# thermometer_temp_sense.net
KiCad netlist of a schematic drawn in EAGLE
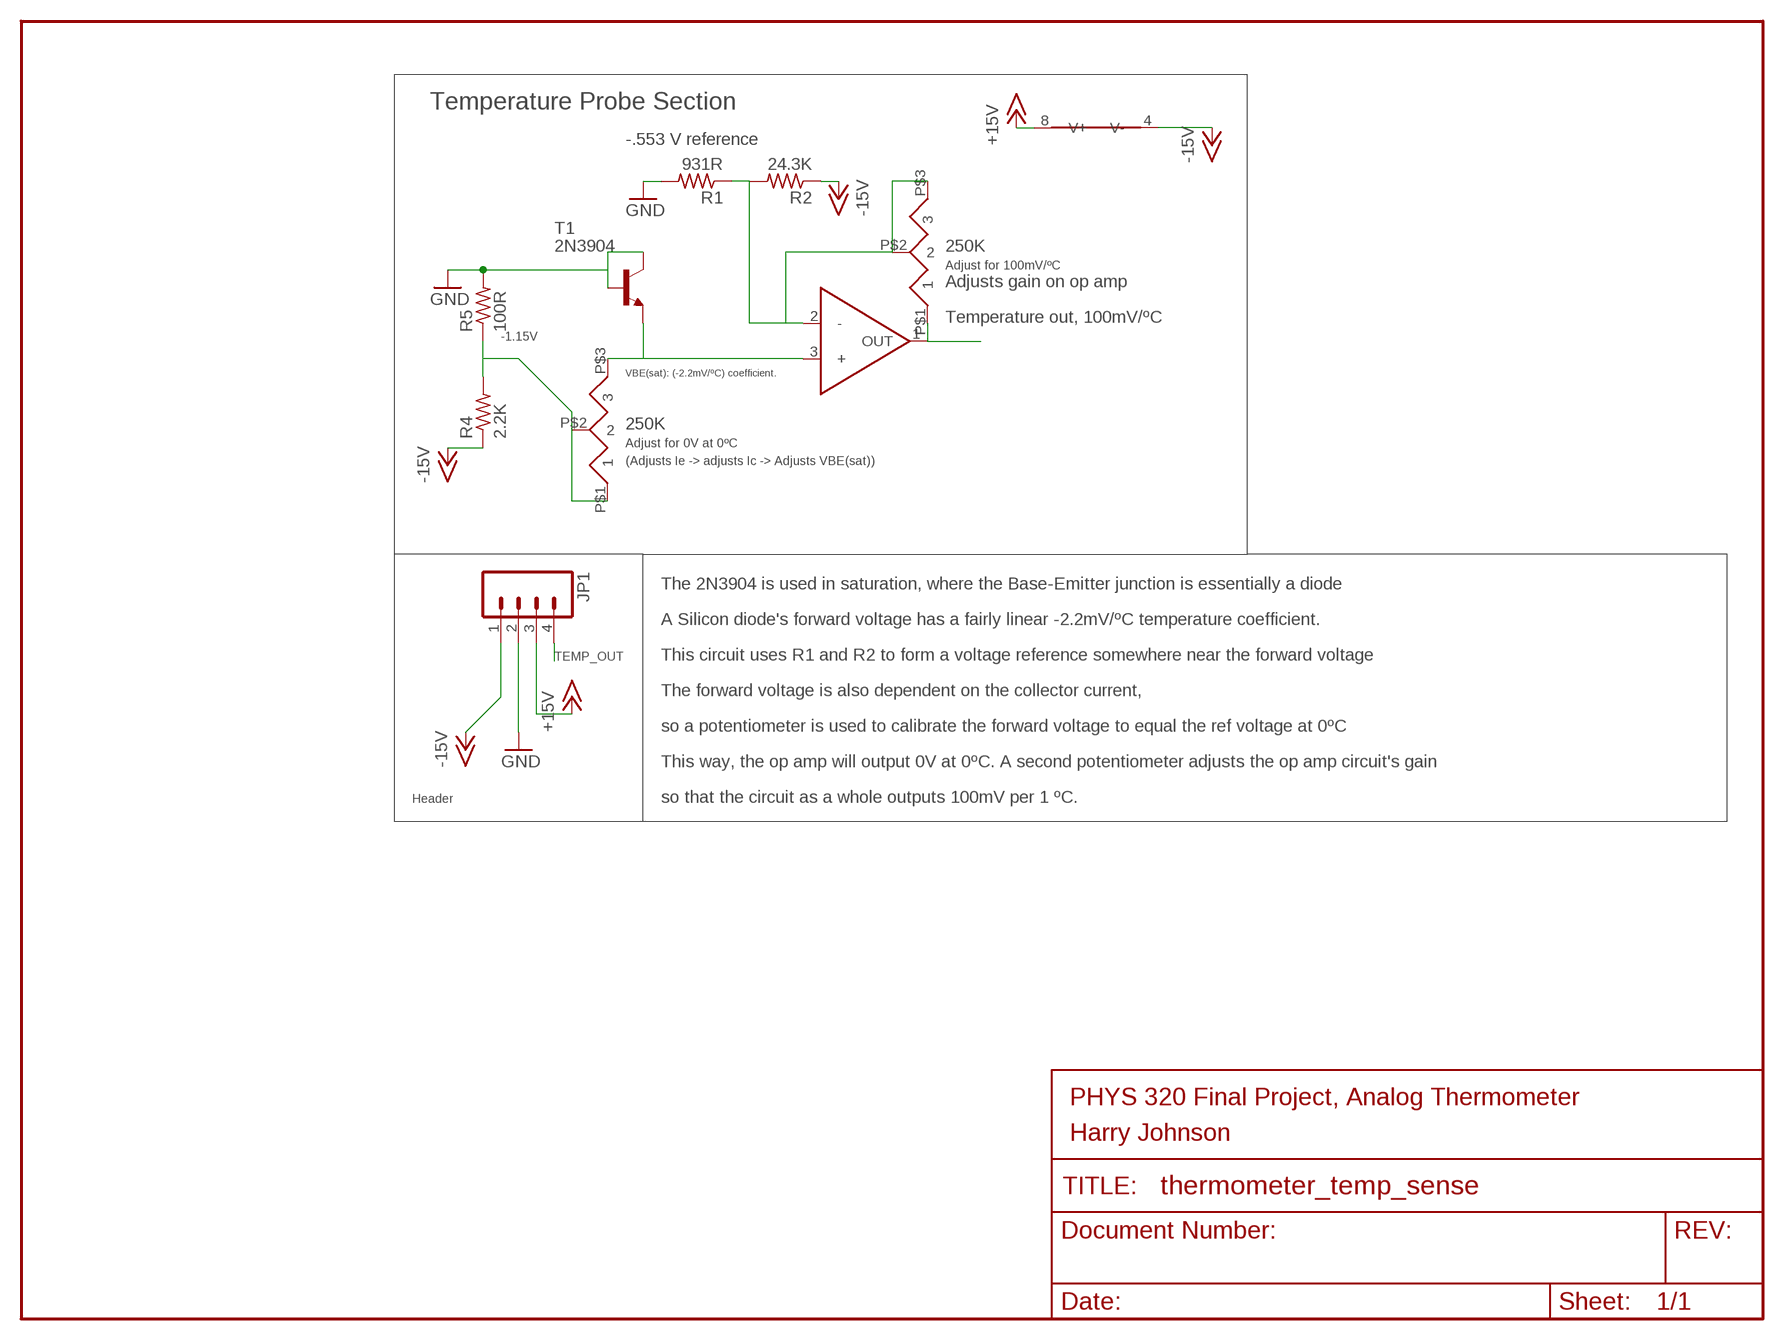
[diagram p0: schematic, sheet 1]

(export (version "E")
  (design (tool "Eeschema 10.0.6"))
  (components
    (comp (ref "JP1")
      (value "M04PTH")
      (footprint "eagle-import:1X04")
      (libsource (lib "eagle-import") (part "M04PTH"))
    )
    (comp (ref "R1")
      (value "931R")
      (footprint "eagle-import:0207_10")
      (libsource (lib "eagle-import") (part "R-US_0207/10"))
    )
    (comp (ref "R2")
      (value "24.3K")
      (footprint "eagle-import:0207_10")
      (libsource (lib "eagle-import") (part "R-US_0207/10"))
    )
    (comp (ref "R4")
      (value "2.2K")
      (footprint "eagle-import:0207_10")
      (libsource (lib "eagle-import") (part "R-US_0207/10"))
    )
    (comp (ref "R5")
      (value "100R")
      (footprint "eagle-import:0207_10")
      (libsource (lib "eagle-import") (part "R-US_0207/10"))
    )
    (comp (ref "T1")
      (value "2N3904")
      (footprint "eagle-import:TO92-EBC-OVAL")
      (libsource (lib "eagle-import") (part "2N2222"))
    )
    (comp (ref "U$1")
      (value "TS522IN")
      (footprint "eagle-import:DIL08")
      (libsource (lib "eagle-import") (part "TS522IN"))
    )
    (comp (ref "U$2")
      (value "250K")
      (footprint "eagle-import:PV36Y254C01B00")
      (libsource (lib "eagle-import") (part "POT"))
    )
    (comp (ref "U$3")
      (value "250K")
      (footprint "eagle-import:PV36Y254C01B00")
      (libsource (lib "eagle-import") (part "POT"))
    )
  )
  (nets
    (net (code "1") (name "+15V") (class "Default")
      (node (ref "JP1") (pin "3") (pinfunction "3_3") (pintype "passive"))
      (node (ref "U$1") (pin "8") (pinfunction "V+_8") (pintype "bidirectional"))
    )
    (net (code "2") (name "-15V") (class "Default")
      (node (ref "JP1") (pin "1") (pinfunction "1_1") (pintype "passive"))
      (node (ref "R2") (pin "1") (pinfunction "1_1") (pintype "passive"))
      (node (ref "R4") (pin "1") (pinfunction "1_1") (pintype "passive"))
      (node (ref "U$1") (pin "4") (pinfunction "V-_4") (pintype "bidirectional"))
    )
    (net (code "3") (name "/TEMP_OUT") (class "Default")
      (node (ref "JP1") (pin "4") (pinfunction "4_4") (pintype "passive"))
      (node (ref "U$1") (pin "1") (pinfunction "OUT_1") (pintype "bidirectional"))
      (node (ref "U$3") (pin "P$1") (pinfunction "1_P$1") (pintype "bidirectional"))
    )
    (net (code "4") (name "GND") (class "Default")
      (node (ref "JP1") (pin "2") (pinfunction "2_2") (pintype "passive"))
      (node (ref "R1") (pin "2") (pinfunction "2_2") (pintype "passive"))
      (node (ref "R5") (pin "2") (pinfunction "2_2") (pintype "passive"))
      (node (ref "T1") (pin "B") (pinfunction "B_B") (pintype "passive"))
      (node (ref "T1") (pin "C") (pinfunction "C_C") (pintype "passive"))
    )
    (net (code "5") (name "Net-(U$1A-+)") (class "Default")
      (node (ref "T1") (pin "E") (pinfunction "E_E") (pintype "passive"))
      (node (ref "U$1") (pin "3") (pinfunction "+_3") (pintype "bidirectional"))
      (node (ref "U$2") (pin "P$3") (pinfunction "3_P$3") (pintype "bidirectional"))
    )
    (net (code "6") (name "Net-(U$1A--)") (class "Default")
      (node (ref "R1") (pin "1") (pinfunction "1_1") (pintype "passive"))
      (node (ref "R2") (pin "2") (pinfunction "2_2") (pintype "passive"))
      (node (ref "U$1") (pin "2") (pinfunction "-_2") (pintype "bidirectional"))
      (node (ref "U$3") (pin "P$2") (pinfunction "2_P$2") (pintype "bidirectional"))
      (node (ref "U$3") (pin "P$3") (pinfunction "3_P$3") (pintype "bidirectional"))
    )
    (net (code "7") (name "Net-(U$2-1)") (class "Default")
      (node (ref "R4") (pin "2") (pinfunction "2_2") (pintype "passive"))
      (node (ref "R5") (pin "1") (pinfunction "1_1") (pintype "passive"))
      (node (ref "U$2") (pin "P$1") (pinfunction "1_P$1") (pintype "bidirectional"))
      (node (ref "U$2") (pin "P$2") (pinfunction "2_P$2") (pintype "bidirectional"))
    )
  )
)
